# speculator_major_mainboard_96mm_v2_1.net
KiCad netlist of a schematic drawn in EAGLE
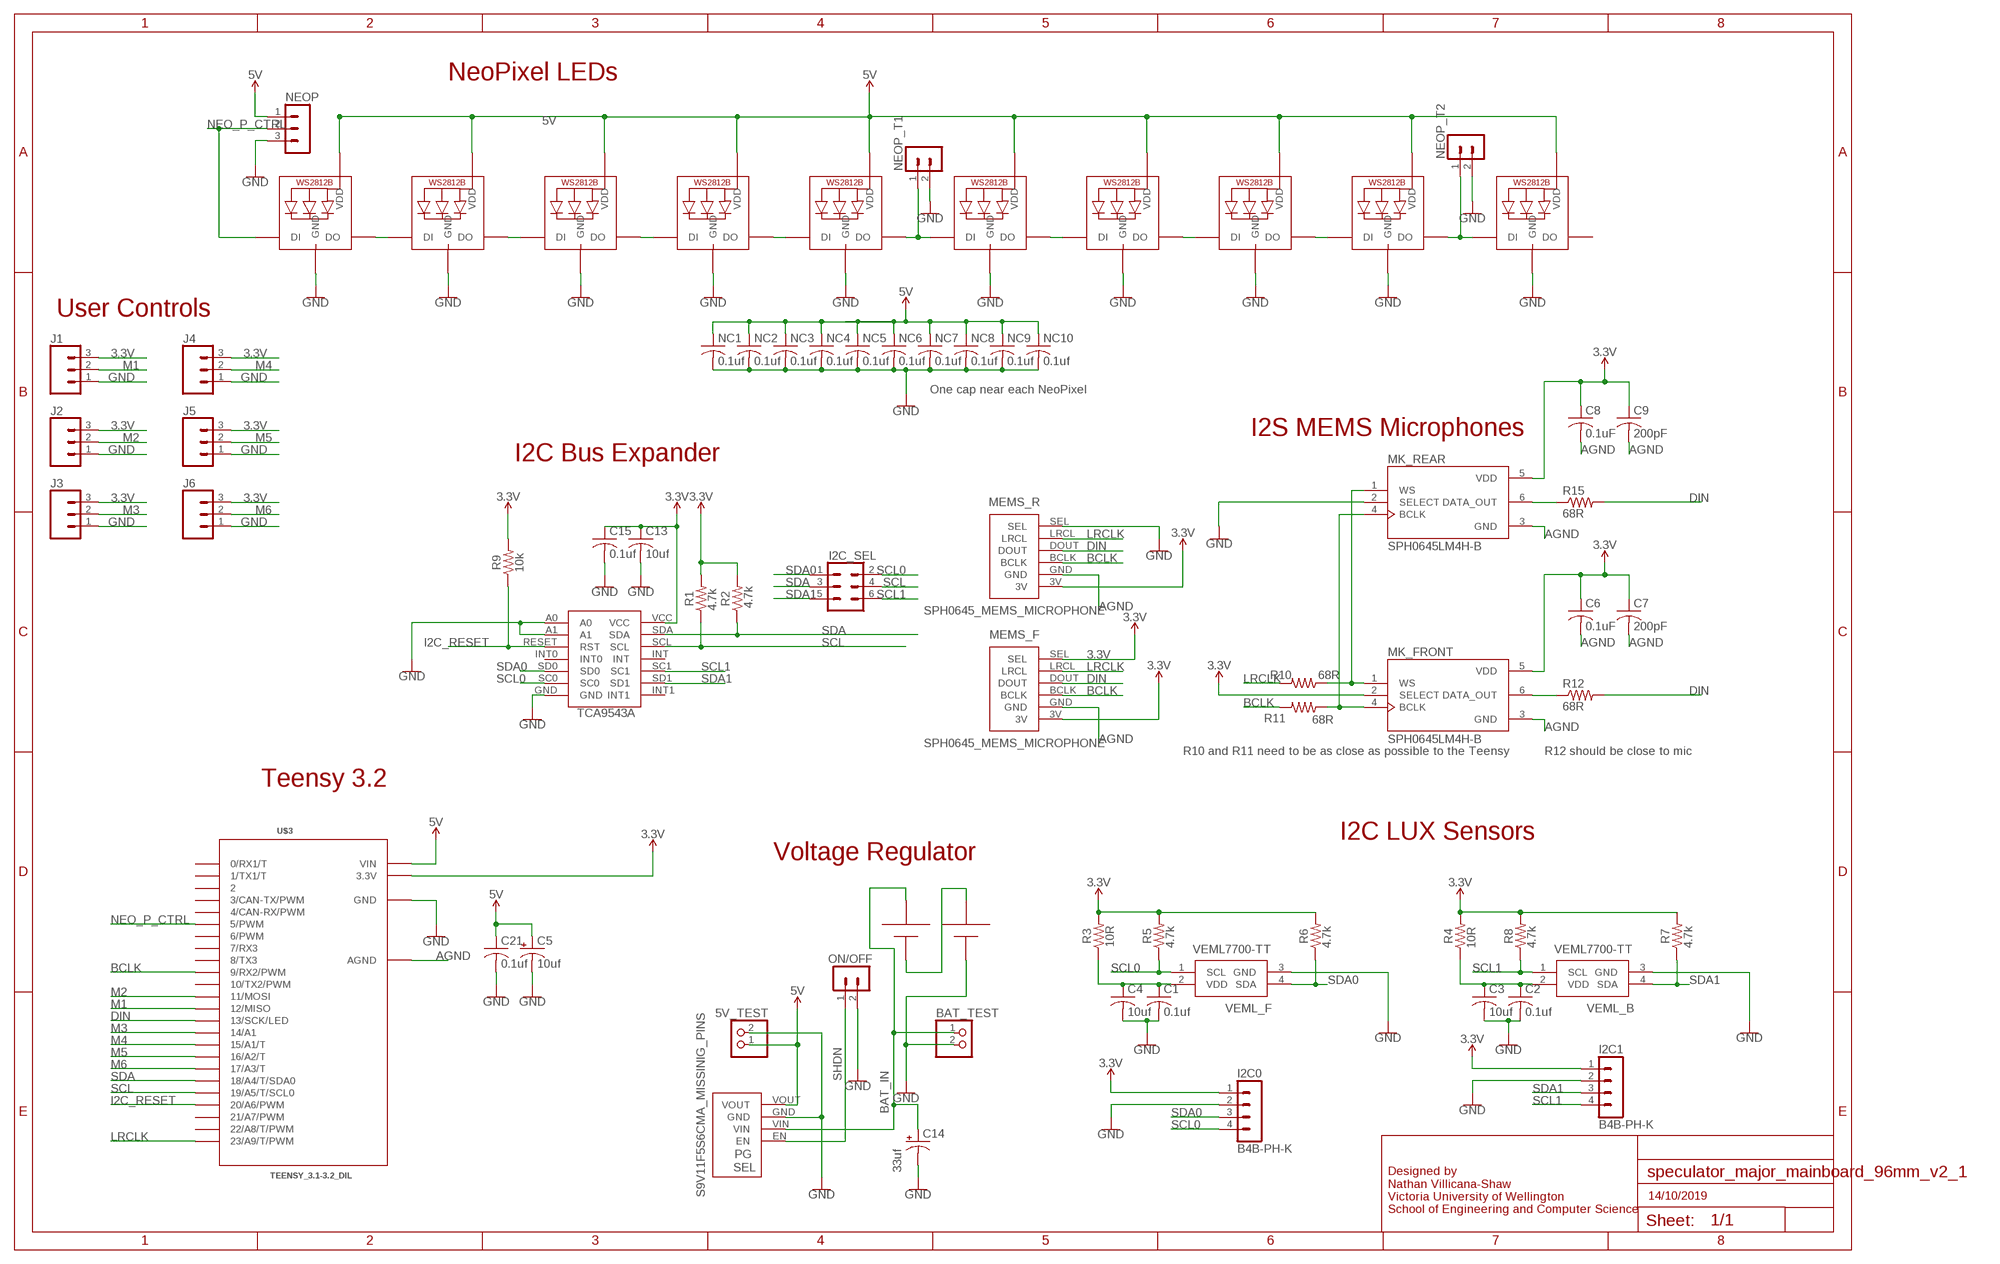
[diagram p0: schematic, sheet 1]

(export (version "E")
  (design (tool "Eeschema 10.0.6"))
  (components
    (comp (ref "5V_TEST")
      (value "PINHD-1X2")
      (footprint "eagle-import:1X02")
      (libsource (lib "eagle-import") (part "PINHD-1X2"))
    )
    (comp (ref "BAT_TEST")
      (value "PINHD-1X2")
      (footprint "eagle-import:1X02")
      (libsource (lib "eagle-import") (part "PINHD-1X2"))
    )
    (comp (ref "C1")
      (value "0.1uf")
      (footprint "eagle-import:C1206K")
      (libsource (lib "eagle-import") (part "C-USC1206K"))
    )
    (comp (ref "C2")
      (value "0.1uf")
      (footprint "eagle-import:C1206K")
      (libsource (lib "eagle-import") (part "C-USC1206K"))
    )
    (comp (ref "C3")
      (value "10uf")
      (footprint "eagle-import:C1206K")
      (libsource (lib "eagle-import") (part "C-USC1206K"))
    )
    (comp (ref "C4")
      (value "10uf")
      (footprint "eagle-import:C1206K")
      (libsource (lib "eagle-import") (part "C-USC1206K"))
    )
    (comp (ref "C5")
      (value "10uf")
      (footprint "eagle-import:E2,5-6")
      (libsource (lib "eagle-import") (part "CPOL-USE2.5-6"))
    )
    (comp (ref "C6")
      (value "0.1uF")
      (footprint "eagle-import:C1206K")
      (libsource (lib "eagle-import") (part "C-USC1206K"))
    )
    (comp (ref "C7")
      (value "200pF")
      (footprint "eagle-import:C1206K")
      (libsource (lib "eagle-import") (part "C-USC1206K"))
    )
    (comp (ref "C8")
      (value "0.1uF")
      (footprint "eagle-import:C1206K")
      (libsource (lib "eagle-import") (part "C-USC1206K"))
    )
    (comp (ref "C9")
      (value "200pF")
      (footprint "eagle-import:C1206K")
      (libsource (lib "eagle-import") (part "C-USC1206K"))
    )
    (comp (ref "C13")
      (value "10uf")
      (footprint "eagle-import:C1206K")
      (libsource (lib "eagle-import") (part "C-USC1206K"))
    )
    (comp (ref "C14")
      (value "33uf")
      (footprint "eagle-import:E2-5")
      (libsource (lib "eagle-import") (part "CPOL-USE2-5"))
    )
    (comp (ref "C15")
      (value "0.1uf")
      (footprint "eagle-import:C1206K")
      (libsource (lib "eagle-import") (part "C-USC1206K"))
    )
    (comp (ref "C21")
      (value "0.1uf")
      (footprint "eagle-import:C1206K")
      (libsource (lib "eagle-import") (part "C-USC1206K"))
    )
    (comp (ref "I2C0")
      (value "B4B-PH-K")
      (footprint "eagle-import:B4B-PH-K")
      (libsource (lib "eagle-import") (part "B4B-PH-K"))
    )
    (comp (ref "I2C1")
      (value "B4B-PH-K")
      (footprint "eagle-import:B4B-PH-K")
      (libsource (lib "eagle-import") (part "B4B-PH-K"))
    )
    (comp (ref "I2C_SEL")
      (value "FEMALE 2x3")
      (footprint "eagle-import:2X3")
      (libsource (lib "eagle-import") (part "CONN_03X2FEMALE"))
    )
    (comp (ref "J1")
      (value "CONN_03")
      (footprint "eagle-import:1X03")
      (libsource (lib "eagle-import") (part "CONN_03"))
    )
    (comp (ref "J2")
      (value "CONN_03")
      (footprint "eagle-import:1X03")
      (libsource (lib "eagle-import") (part "CONN_03"))
    )
    (comp (ref "J3")
      (value "CONN_03")
      (footprint "eagle-import:1X03")
      (libsource (lib "eagle-import") (part "CONN_03"))
    )
    (comp (ref "J4")
      (value "CONN_03")
      (footprint "eagle-import:1X03")
      (libsource (lib "eagle-import") (part "CONN_03"))
    )
    (comp (ref "J5")
      (value "CONN_03")
      (footprint "eagle-import:1X03")
      (libsource (lib "eagle-import") (part "CONN_03"))
    )
    (comp (ref "J6")
      (value "CONN_03")
      (footprint "eagle-import:1X03")
      (libsource (lib "eagle-import") (part "CONN_03"))
    )
    (comp (ref "MEMS_F")
      (value "SPH0645_MEMS_MICROPHONE")
      (footprint "eagle-import:SPH0645")
      (libsource (lib "eagle-import") (part "SPH0645_MEMS_MICROPHONE"))
    )
    (comp (ref "MEMS_R")
      (value "SPH0645_MEMS_MICROPHONE")
      (footprint "eagle-import:SPH0645")
      (libsource (lib "eagle-import") (part "SPH0645_MEMS_MICROPHONE"))
    )
    (comp (ref "MK_FRONT")
      (value "SPH0645LM4H-B")
      (footprint "eagle-import:MIC_SPH0645LM4H-B")
      (fields (field (name "DIGI-KEY_PART_NUMBER") "423-1405-1-ND") (field (name "MF") "Knowles"))
      (libsource (lib "eagle-import") (part "SPH0645LM4H-B"))
    )
    (comp (ref "MK_REAR")
      (value "SPH0645LM4H-B")
      (footprint "eagle-import:MIC_SPH0645LM4H-B")
      (fields (field (name "DIGI-KEY_PART_NUMBER") "423-1405-1-ND") (field (name "MF") "Knowles"))
      (libsource (lib "eagle-import") (part "SPH0645LM4H-B"))
    )
    (comp (ref "NC1")
      (value "0.1uf")
      (footprint "eagle-import:C1206K")
      (libsource (lib "eagle-import") (part "C-USC1206K"))
    )
    (comp (ref "NC2")
      (value "0.1uf")
      (footprint "eagle-import:C1206K")
      (libsource (lib "eagle-import") (part "C-USC1206K"))
    )
    (comp (ref "NC3")
      (value "0.1uf")
      (footprint "eagle-import:C1206K")
      (libsource (lib "eagle-import") (part "C-USC1206K"))
    )
    (comp (ref "NC4")
      (value "0.1uf")
      (footprint "eagle-import:C1206K")
      (libsource (lib "eagle-import") (part "C-USC1206K"))
    )
    (comp (ref "NC5")
      (value "0.1uf")
      (footprint "eagle-import:C1206K")
      (libsource (lib "eagle-import") (part "C-USC1206K"))
    )
    (comp (ref "NC6")
      (value "0.1uf")
      (footprint "eagle-import:C1206K")
      (libsource (lib "eagle-import") (part "C-USC1206K"))
    )
    (comp (ref "NC7")
      (value "0.1uf")
      (footprint "eagle-import:C1206K")
      (libsource (lib "eagle-import") (part "C-USC1206K"))
    )
    (comp (ref "NC8")
      (value "0.1uf")
      (footprint "eagle-import:C1206K")
      (libsource (lib "eagle-import") (part "C-USC1206K"))
    )
    (comp (ref "NC9")
      (value "0.1uf")
      (footprint "eagle-import:C1206K")
      (libsource (lib "eagle-import") (part "C-USC1206K"))
    )
    (comp (ref "NC10")
      (value "0.1uf")
      (footprint "eagle-import:C1206K")
      (libsource (lib "eagle-import") (part "C-USC1206K"))
    )
    (comp (ref "NEO1")
      (value "WS2812B5050")
      (footprint "eagle-import:WS2812B")
      (libsource (lib "eagle-import") (part "WS2812B5050"))
    )
    (comp (ref "NEO2")
      (value "WS2812B5050")
      (footprint "eagle-import:WS2812B")
      (libsource (lib "eagle-import") (part "WS2812B5050"))
    )
    (comp (ref "NEO3")
      (value "WS2812B5050")
      (footprint "eagle-import:WS2812B")
      (libsource (lib "eagle-import") (part "WS2812B5050"))
    )
    (comp (ref "NEO4")
      (value "WS2812B5050")
      (footprint "eagle-import:WS2812B")
      (libsource (lib "eagle-import") (part "WS2812B5050"))
    )
    (comp (ref "NEO5")
      (value "WS2812B5050")
      (footprint "eagle-import:WS2812B")
      (libsource (lib "eagle-import") (part "WS2812B5050"))
    )
    (comp (ref "NEO6")
      (value "WS2812B5050")
      (footprint "eagle-import:WS2812B")
      (libsource (lib "eagle-import") (part "WS2812B5050"))
    )
    (comp (ref "NEO7")
      (value "WS2812B5050")
      (footprint "eagle-import:WS2812B")
      (libsource (lib "eagle-import") (part "WS2812B5050"))
    )
    (comp (ref "NEO8")
      (value "WS2812B5050")
      (footprint "eagle-import:WS2812B")
      (libsource (lib "eagle-import") (part "WS2812B5050"))
    )
    (comp (ref "NEO9")
      (value "WS2812B5050")
      (footprint "eagle-import:WS2812B")
      (libsource (lib "eagle-import") (part "WS2812B5050"))
    )
    (comp (ref "NEO10")
      (value "WS2812B5050")
      (footprint "eagle-import:WS2812B")
      (libsource (lib "eagle-import") (part "WS2812B5050"))
    )
    (comp (ref "NEOP")
      (value "B3B-PH-K")
      (footprint "eagle-import:B3B-PH-K")
      (libsource (lib "eagle-import") (part "B3B-PH-K"))
    )
    (comp (ref "NEOP_T1")
      (value "B2B-PH-K")
      (footprint "eagle-import:B2B-PH-K")
      (libsource (lib "eagle-import") (part "B2B-PH-K"))
    )
    (comp (ref "NEOP_T2")
      (value "B2B-PH-K")
      (footprint "eagle-import:B2B-PH-K")
      (libsource (lib "eagle-import") (part "B2B-PH-K"))
    )
    (comp (ref "ON/OFF")
      (value "B2B-PH-K")
      (footprint "eagle-import:B2B-PH-K")
      (libsource (lib "eagle-import") (part "B2B-PH-K"))
    )
    (comp (ref "R1")
      (value "4.7k")
      (footprint "eagle-import:R1206W")
      (libsource (lib "eagle-import") (part "R-US_R1206W"))
    )
    (comp (ref "R2")
      (value "4.7k")
      (footprint "eagle-import:R1206W")
      (libsource (lib "eagle-import") (part "R-US_R1206W"))
    )
    (comp (ref "R3")
      (value "10R")
      (footprint "eagle-import:R1206W")
      (libsource (lib "eagle-import") (part "R-US_R1206W"))
    )
    (comp (ref "R4")
      (value "10R")
      (footprint "eagle-import:R1206W")
      (libsource (lib "eagle-import") (part "R-US_R1206W"))
    )
    (comp (ref "R5")
      (value "4.7k")
      (footprint "eagle-import:R1206W")
      (libsource (lib "eagle-import") (part "R-US_R1206W"))
    )
    (comp (ref "R6")
      (value "4.7k")
      (footprint "eagle-import:R1206W")
      (libsource (lib "eagle-import") (part "R-US_R1206W"))
    )
    (comp (ref "R7")
      (value "4.7k")
      (footprint "eagle-import:R1206W")
      (libsource (lib "eagle-import") (part "R-US_R1206W"))
    )
    (comp (ref "R8")
      (value "4.7k")
      (footprint "eagle-import:R1206W")
      (libsource (lib "eagle-import") (part "R-US_R1206W"))
    )
    (comp (ref "R9")
      (value "10k")
      (footprint "eagle-import:R1206W")
      (libsource (lib "eagle-import") (part "R-US_R1206W"))
    )
    (comp (ref "R10")
      (value "68R")
      (footprint "eagle-import:M1206")
      (libsource (lib "eagle-import") (part "R-US_M1206"))
    )
    (comp (ref "R11")
      (value "68R")
      (footprint "eagle-import:M1206")
      (libsource (lib "eagle-import") (part "R-US_M1206"))
    )
    (comp (ref "R12")
      (value "68R")
      (footprint "eagle-import:M1206")
      (libsource (lib "eagle-import") (part "R-US_M1206"))
    )
    (comp (ref "R15")
      (value "68R")
      (footprint "eagle-import:M1206")
      (libsource (lib "eagle-import") (part "R-US_M1206"))
    )
    (comp (ref "U$1")
      (value "TCA9543A")
      (footprint "eagle-import:SO14")
      (libsource (lib "eagle-import") (part "TCA9543A"))
    )
    (comp (ref "U$2")
      (value "BK-18650-PC4")
      (footprint "eagle-import:18650-PC4")
      (fields (field (name "MF") "MPD"))
      (libsource (lib "eagle-import") (part "BK-18650-PC4"))
    )
    (comp (ref "U$3")
      (value "TEENSY_3.1-3.2_DIL")
      (footprint "eagle-import:TEENSY_3.0-3.2&LC_DIL")
      (libsource (lib "eagle-import") (part "TEENSY_3.1-3.2_DIL"))
    )
    (comp (ref "U$6")
      (value "S9V11F5S6CMA_MISSINIG_PINS")
      (footprint "eagle-import:S9V11F3S5CMA_MISSING_PINS")
      (libsource (lib "eagle-import") (part "S9V11F5S6CMA_MISSINIG_PINS"))
    )
    (comp (ref "VEML_B")
      (value "VEML7700-TT")
      (footprint "eagle-import:VEML7700")
      (fields (field (name "MOUSER_PART_NUMBER") "78-VEML7700-TT") (field (name "RS_PART_NUMBER") "1226791P"))
      (libsource (lib "eagle-import") (part "VEML7700-TT"))
    )
    (comp (ref "VEML_F")
      (value "VEML7700-TT")
      (footprint "eagle-import:VEML7700")
      (fields (field (name "MOUSER_PART_NUMBER") "78-VEML7700-TT") (field (name "RS_PART_NUMBER") "1226791P"))
      (libsource (lib "eagle-import") (part "VEML7700-TT"))
    )
  )
  (nets
    (net (code "1") (name "/AGND") (class "Default")
      (node (ref "C6") (pin "2") (pinfunction "2_2") (pintype "passive"))
      (node (ref "C7") (pin "2") (pinfunction "2_2") (pintype "passive"))
      (node (ref "C8") (pin "2") (pinfunction "2_2") (pintype "passive"))
      (node (ref "C9") (pin "2") (pinfunction "2_2") (pintype "passive"))
      (node (ref "MEMS_F") (pin "GND") (pinfunction "GND_GND") (pintype "bidirectional"))
      (node (ref "MEMS_R") (pin "GND") (pinfunction "GND_GND") (pintype "bidirectional"))
      (node (ref "MK_FRONT") (pin "3") (pinfunction "GND_3") (pintype "power_in"))
      (node (ref "MK_REAR") (pin "3") (pinfunction "GND_3") (pintype "power_in"))
      (node (ref "U$3") (pin "AGND") (pinfunction "AGND_AGND") (pintype "power_in"))
    )
    (net (code "2") (name "/BAT_IN") (class "Default")
      (node (ref "BAT_TEST") (pin "1") (pinfunction "1_1") (pintype "passive"))
      (node (ref "C14") (pin "+") (pinfunction "+_+") (pintype "passive"))
      (node (ref "U$2") (pin "+1") (pinfunction "+1_+1") (pintype "bidirectional"))
      (node (ref "U$6") (pin "VIN") (pinfunction "VIN_VIN") (pintype "bidirectional"))
    )
    (net (code "3") (name "/BCLK") (class "Default")
      (node (ref "MEMS_F") (pin "BCLK") (pinfunction "BCLK_BCLK") (pintype "bidirectional"))
      (node (ref "MEMS_R") (pin "BCLK") (pinfunction "BCLK_BCLK") (pintype "bidirectional"))
      (node (ref "R11") (pin "2") (pinfunction "2_2") (pintype "passive"))
      (node (ref "U$3") (pin "9") (pinfunction "9/RX2/PWM_9") (pintype "bidirectional"))
    )
    (net (code "4") (name "/DIN") (class "Default")
      (node (ref "MEMS_F") (pin "DOUT") (pinfunction "DOUT_DOUT") (pintype "bidirectional"))
      (node (ref "MEMS_R") (pin "DOUT") (pinfunction "DOUT_DOUT") (pintype "bidirectional"))
      (node (ref "R12") (pin "2") (pinfunction "2_2") (pintype "passive"))
      (node (ref "R15") (pin "2") (pinfunction "2_2") (pintype "passive"))
      (node (ref "U$3") (pin "13") (pinfunction "13/SCK/LED_13") (pintype "bidirectional"))
    )
    (net (code "5") (name "/I2C_RESET") (class "Default")
      (node (ref "R9") (pin "1") (pinfunction "1_1") (pintype "passive"))
      (node (ref "U$1") (pin "RESET") (pinfunction "RST_RESET") (pintype "bidirectional"))
      (node (ref "U$3") (pin "20/A6") (pinfunction "20/A6/PWM_20/A6") (pintype "bidirectional"))
    )
    (net (code "6") (name "/LRCLK") (class "Default")
      (node (ref "MEMS_F") (pin "LRCL") (pinfunction "LRCL_LRCL") (pintype "bidirectional"))
      (node (ref "MEMS_R") (pin "LRCL") (pinfunction "LRCL_LRCL") (pintype "bidirectional"))
      (node (ref "R10") (pin "2") (pinfunction "2_2") (pintype "passive"))
      (node (ref "U$3") (pin "23/A9") (pinfunction "23/A9/T/PWM_23/A9") (pintype "bidirectional"))
    )
    (net (code "7") (name "/M1") (class "Default")
      (node (ref "J1") (pin "2") (pinfunction "2_2") (pintype "passive"))
      (node (ref "U$3") (pin "12") (pinfunction "12/MISO_12") (pintype "bidirectional"))
    )
    (net (code "8") (name "/M2") (class "Default")
      (node (ref "J2") (pin "2") (pinfunction "2_2") (pintype "passive"))
      (node (ref "U$3") (pin "11") (pinfunction "11/MOSI_11") (pintype "bidirectional"))
    )
    (net (code "9") (name "/M3") (class "Default")
      (node (ref "J3") (pin "2") (pinfunction "2_2") (pintype "passive"))
      (node (ref "U$3") (pin "14/A0") (pinfunction "14/A1_14/A0") (pintype "bidirectional"))
    )
    (net (code "10") (name "/M4") (class "Default")
      (node (ref "J4") (pin "2") (pinfunction "2_2") (pintype "passive"))
      (node (ref "U$3") (pin "15/A1") (pinfunction "15/A1/T_15/A1") (pintype "bidirectional"))
    )
    (net (code "11") (name "/M5") (class "Default")
      (node (ref "J5") (pin "2") (pinfunction "2_2") (pintype "passive"))
      (node (ref "U$3") (pin "16/A2") (pinfunction "16/A2/T_16/A2") (pintype "bidirectional"))
    )
    (net (code "12") (name "/M6") (class "Default")
      (node (ref "J6") (pin "2") (pinfunction "2_2") (pintype "passive"))
      (node (ref "U$3") (pin "17/A3") (pinfunction "17/A3/T_17/A3") (pintype "bidirectional"))
    )
    (net (code "13") (name "/NEO_P_CTRL") (class "Default")
      (node (ref "NEO1") (pin "4-DIN") (pinfunction "DI_4-DIN") (pintype "input"))
      (node (ref "NEOP") (pin "2") (pinfunction "2_2") (pintype "passive"))
      (node (ref "U$3") (pin "5") (pinfunction "5/PWM_5") (pintype "bidirectional"))
    )
    (net (code "14") (name "/SCL") (class "Default")
      (node (ref "I2C_SEL") (pin "4") (pinfunction "4_4") (pintype "bidirectional"))
      (node (ref "R1") (pin "1") (pinfunction "1_1") (pintype "passive"))
      (node (ref "U$1") (pin "SCL") (pinfunction "SCL_SCL") (pintype "bidirectional"))
      (node (ref "U$3") (pin "19/A5") (pinfunction "19/A5/T/SCL0_19/A5") (pintype "bidirectional"))
    )
    (net (code "15") (name "/SCL0") (class "Default")
      (node (ref "I2C0") (pin "4") (pinfunction "4_4") (pintype "passive"))
      (node (ref "I2C_SEL") (pin "2") (pinfunction "2_2") (pintype "bidirectional"))
      (node (ref "R5") (pin "1") (pinfunction "1_1") (pintype "passive"))
      (node (ref "U$1") (pin "SC0") (pinfunction "SC0_SC0") (pintype "bidirectional"))
      (node (ref "VEML_F") (pin "1") (pinfunction "SCL_1") (pintype "bidirectional"))
    )
    (net (code "16") (name "/SCL1") (class "Default")
      (node (ref "I2C1") (pin "4") (pinfunction "4_4") (pintype "passive"))
      (node (ref "I2C_SEL") (pin "6") (pinfunction "6_6") (pintype "bidirectional"))
      (node (ref "R8") (pin "1") (pinfunction "1_1") (pintype "passive"))
      (node (ref "U$1") (pin "SC1") (pinfunction "SC1_SC1") (pintype "bidirectional"))
      (node (ref "VEML_B") (pin "1") (pinfunction "SCL_1") (pintype "bidirectional"))
    )
    (net (code "17") (name "/SDA") (class "Default")
      (node (ref "I2C_SEL") (pin "3") (pinfunction "3_3") (pintype "bidirectional"))
      (node (ref "R2") (pin "1") (pinfunction "1_1") (pintype "passive"))
      (node (ref "U$1") (pin "SDA") (pinfunction "SDA_SDA") (pintype "bidirectional"))
      (node (ref "U$3") (pin "18/A4") (pinfunction "18/A4/T/SDA0_18/A4") (pintype "bidirectional"))
    )
    (net (code "18") (name "/SDA0") (class "Default")
      (node (ref "I2C0") (pin "3") (pinfunction "3_3") (pintype "passive"))
      (node (ref "I2C_SEL") (pin "1") (pinfunction "1_1") (pintype "bidirectional"))
      (node (ref "R6") (pin "1") (pinfunction "1_1") (pintype "passive"))
      (node (ref "U$1") (pin "SD0") (pinfunction "SD0_SD0") (pintype "bidirectional"))
      (node (ref "VEML_F") (pin "4") (pinfunction "SDA_4") (pintype "bidirectional"))
    )
    (net (code "19") (name "/SDA1") (class "Default")
      (node (ref "I2C1") (pin "3") (pinfunction "3_3") (pintype "passive"))
      (node (ref "I2C_SEL") (pin "5") (pinfunction "5_5") (pintype "bidirectional"))
      (node (ref "R7") (pin "1") (pinfunction "1_1") (pintype "passive"))
      (node (ref "U$1") (pin "SD1") (pinfunction "SD1_SD1") (pintype "bidirectional"))
      (node (ref "VEML_B") (pin "4") (pinfunction "SDA_4") (pintype "bidirectional"))
    )
    (net (code "20") (name "/SHDN") (class "Default")
      (node (ref "ON/OFF") (pin "1") (pinfunction "1_1") (pintype "passive"))
      (node (ref "U$6") (pin "EN") (pinfunction "EN_EN") (pintype "bidirectional"))
    )
    (net (code "21") (name "3.3V") (class "Default")
      (node (ref "C13") (pin "1") (pinfunction "1_1") (pintype "passive"))
      (node (ref "C15") (pin "1") (pinfunction "1_1") (pintype "passive"))
      (node (ref "C6") (pin "1") (pinfunction "1_1") (pintype "passive"))
      (node (ref "C7") (pin "1") (pinfunction "1_1") (pintype "passive"))
      (node (ref "C8") (pin "1") (pinfunction "1_1") (pintype "passive"))
      (node (ref "C9") (pin "1") (pinfunction "1_1") (pintype "passive"))
      (node (ref "I2C0") (pin "1") (pinfunction "1_1") (pintype "passive"))
      (node (ref "I2C1") (pin "1") (pinfunction "1_1") (pintype "passive"))
      (node (ref "J1") (pin "3") (pinfunction "3_3") (pintype "passive"))
      (node (ref "J2") (pin "3") (pinfunction "3_3") (pintype "passive"))
      (node (ref "J3") (pin "3") (pinfunction "3_3") (pintype "passive"))
      (node (ref "J4") (pin "3") (pinfunction "3_3") (pintype "passive"))
      (node (ref "J5") (pin "3") (pinfunction "3_3") (pintype "passive"))
      (node (ref "J6") (pin "3") (pinfunction "3_3") (pintype "passive"))
      (node (ref "MEMS_F") (pin "3V") (pinfunction "3V_3V") (pintype "bidirectional"))
      (node (ref "MEMS_F") (pin "SEL") (pinfunction "SEL_SEL") (pintype "bidirectional"))
      (node (ref "MEMS_R") (pin "3V") (pinfunction "3V_3V") (pintype "bidirectional"))
      (node (ref "MK_FRONT") (pin "2") (pinfunction "SELECT_2") (pintype "input"))
      (node (ref "MK_FRONT") (pin "5") (pinfunction "VDD_5") (pintype "power_in"))
      (node (ref "MK_REAR") (pin "5") (pinfunction "VDD_5") (pintype "power_in"))
      (node (ref "R1") (pin "2") (pinfunction "2_2") (pintype "passive"))
      (node (ref "R2") (pin "2") (pinfunction "2_2") (pintype "passive"))
      (node (ref "R3") (pin "2") (pinfunction "2_2") (pintype "passive"))
      (node (ref "R4") (pin "2") (pinfunction "2_2") (pintype "passive"))
      (node (ref "R5") (pin "2") (pinfunction "2_2") (pintype "passive"))
      (node (ref "R6") (pin "2") (pinfunction "2_2") (pintype "passive"))
      (node (ref "R7") (pin "2") (pinfunction "2_2") (pintype "passive"))
      (node (ref "R8") (pin "2") (pinfunction "2_2") (pintype "passive"))
      (node (ref "R9") (pin "2") (pinfunction "2_2") (pintype "passive"))
      (node (ref "U$1") (pin "VCC") (pinfunction "VCC_VCC") (pintype "bidirectional"))
      (node (ref "U$3") (pin "3.3V") (pinfunction "3.3V_3.3V") (pintype "power_in"))
    )
    (net (code "22") (name "5V") (class "Default")
      (node (ref "5V_TEST") (pin "1") (pinfunction "1_1") (pintype "passive"))
      (node (ref "C21") (pin "1") (pinfunction "1_1") (pintype "passive"))
      (node (ref "C5") (pin "+") (pinfunction "+_+") (pintype "passive"))
      (node (ref "NC1") (pin "1") (pinfunction "1_1") (pintype "passive"))
      (node (ref "NC10") (pin "1") (pinfunction "1_1") (pintype "passive"))
      (node (ref "NC2") (pin "1") (pinfunction "1_1") (pintype "passive"))
      (node (ref "NC3") (pin "1") (pinfunction "1_1") (pintype "passive"))
      (node (ref "NC4") (pin "1") (pinfunction "1_1") (pintype "passive"))
      (node (ref "NC5") (pin "1") (pinfunction "1_1") (pintype "passive"))
      (node (ref "NC6") (pin "1") (pinfunction "1_1") (pintype "passive"))
      (node (ref "NC7") (pin "1") (pinfunction "1_1") (pintype "passive"))
      (node (ref "NC8") (pin "1") (pinfunction "1_1") (pintype "passive"))
      (node (ref "NC9") (pin "1") (pinfunction "1_1") (pintype "passive"))
      (node (ref "NEO1") (pin "1-VDD") (pinfunction "VDD_1-VDD") (pintype "power_in"))
      (node (ref "NEO10") (pin "1-VDD") (pinfunction "VDD_1-VDD") (pintype "power_in"))
      (node (ref "NEO2") (pin "1-VDD") (pinfunction "VDD_1-VDD") (pintype "power_in"))
      (node (ref "NEO3") (pin "1-VDD") (pinfunction "VDD_1-VDD") (pintype "power_in"))
      (node (ref "NEO4") (pin "1-VDD") (pinfunction "VDD_1-VDD") (pintype "power_in"))
      (node (ref "NEO5") (pin "1-VDD") (pinfunction "VDD_1-VDD") (pintype "power_in"))
      (node (ref "NEO6") (pin "1-VDD") (pinfunction "VDD_1-VDD") (pintype "power_in"))
      (node (ref "NEO7") (pin "1-VDD") (pinfunction "VDD_1-VDD") (pintype "power_in"))
      (node (ref "NEO8") (pin "1-VDD") (pinfunction "VDD_1-VDD") (pintype "power_in"))
      (node (ref "NEO9") (pin "1-VDD") (pinfunction "VDD_1-VDD") (pintype "power_in"))
      (node (ref "NEOP") (pin "1") (pinfunction "1_1") (pintype "passive"))
      (node (ref "U$3") (pin "VIN") (pinfunction "VIN_VIN") (pintype "power_in"))
      (node (ref "U$6") (pin "VOUT") (pinfunction "VOUT_VOUT") (pintype "bidirectional"))
    )
    (net (code "23") (name "GND") (class "Default")
      (node (ref "5V_TEST") (pin "2") (pinfunction "2_2") (pintype "passive"))
      (node (ref "BAT_TEST") (pin "2") (pinfunction "2_2") (pintype "passive"))
      (node (ref "C1") (pin "2") (pinfunction "2_2") (pintype "passive"))
      (node (ref "C13") (pin "2") (pinfunction "2_2") (pintype "passive"))
      (node (ref "C14") (pin "-") (pinfunction "-_-") (pintype "passive"))
      (node (ref "C15") (pin "2") (pinfunction "2_2") (pintype "passive"))
      (node (ref "C2") (pin "2") (pinfunction "2_2") (pintype "passive"))
      (node (ref "C21") (pin "2") (pinfunction "2_2") (pintype "passive"))
      (node (ref "C3") (pin "2") (pinfunction "2_2") (pintype "passive"))
      (node (ref "C4") (pin "2") (pinfunction "2_2") (pintype "passive"))
      (node (ref "C5") (pin "-") (pinfunction "-_-") (pintype "passive"))
      (node (ref "I2C0") (pin "2") (pinfunction "2_2") (pintype "passive"))
      (node (ref "I2C1") (pin "2") (pinfunction "2_2") (pintype "passive"))
      (node (ref "J1") (pin "1") (pinfunction "1_1") (pintype "passive"))
      (node (ref "J2") (pin "1") (pinfunction "1_1") (pintype "passive"))
      (node (ref "J3") (pin "1") (pinfunction "1_1") (pintype "passive"))
      (node (ref "J4") (pin "1") (pinfunction "1_1") (pintype "passive"))
      (node (ref "J5") (pin "1") (pinfunction "1_1") (pintype "passive"))
      (node (ref "J6") (pin "1") (pinfunction "1_1") (pintype "passive"))
      (node (ref "MEMS_R") (pin "SEL") (pinfunction "SEL_SEL") (pintype "bidirectional"))
      (node (ref "MK_REAR") (pin "2") (pinfunction "SELECT_2") (pintype "input"))
      (node (ref "NC1") (pin "2") (pinfunction "2_2") (pintype "passive"))
      (node (ref "NC10") (pin "2") (pinfunction "2_2") (pintype "passive"))
      (node (ref "NC2") (pin "2") (pinfunction "2_2") (pintype "passive"))
      (node (ref "NC3") (pin "2") (pinfunction "2_2") (pintype "passive"))
      (node (ref "NC4") (pin "2") (pinfunction "2_2") (pintype "passive"))
      (node (ref "NC5") (pin "2") (pinfunction "2_2") (pintype "passive"))
      (node (ref "NC6") (pin "2") (pinfunction "2_2") (pintype "passive"))
      (node (ref "NC7") (pin "2") (pinfunction "2_2") (pintype "passive"))
      (node (ref "NC8") (pin "2") (pinfunction "2_2") (pintype "passive"))
      (node (ref "NC9") (pin "2") (pinfunction "2_2") (pintype "passive"))
      (node (ref "NEO1") (pin "3-GND") (pinfunction "GND_3-GND") (pintype "power_in"))
      (node (ref "NEO10") (pin "3-GND") (pinfunction "GND_3-GND") (pintype "power_in"))
      (node (ref "NEO2") (pin "3-GND") (pinfunction "GND_3-GND") (pintype "power_in"))
      (node (ref "NEO3") (pin "3-GND") (pinfunction "GND_3-GND") (pintype "power_in"))
      (node (ref "NEO4") (pin "3-GND") (pinfunction "GND_3-GND") (pintype "power_in"))
      (node (ref "NEO5") (pin "3-GND") (pinfunction "GND_3-GND") (pintype "power_in"))
      (node (ref "NEO6") (pin "3-GND") (pinfunction "GND_3-GND") (pintype "power_in"))
      (node (ref "NEO7") (pin "3-GND") (pinfunction "GND_3-GND") (pintype "power_in"))
      (node (ref "NEO8") (pin "3-GND") (pinfunction "GND_3-GND") (pintype "power_in"))
      (node (ref "NEO9") (pin "3-GND") (pinfunction "GND_3-GND") (pintype "power_in"))
      (node (ref "NEOP") (pin "3") (pinfunction "3_3") (pintype "passive"))
      (node (ref "NEOP_T1") (pin "2") (pinfunction "2_2") (pintype "passive"))
      (node (ref "NEOP_T2") (pin "2") (pinfunction "2_2") (pintype "passive"))
      (node (ref "ON/OFF") (pin "2") (pinfunction "2_2") (pintype "passive"))
      (node (ref "U$1") (pin "A0") (pinfunction "A0_A0") (pintype "bidirectional"))
      (node (ref "U$1") (pin "A1") (pinfunction "A1_A1") (pintype "bidirectional"))
      (node (ref "U$1") (pin "GND") (pinfunction "GND_GND") (pintype "bidirectional"))
      (node (ref "U$2") (pin "-2") (pinfunction "-2_-2") (pintype "bidirectional"))
      (node (ref "U$3") (pin "GND") (pinfunction "GND_GND") (pintype "power_in"))
      (node (ref "U$6") (pin "GND") (pinfunction "GND_GND") (pintype "bidirectional"))
      (node (ref "VEML_B") (pin "3") (pinfunction "GND_3") (pintype "bidirectional"))
      (node (ref "VEML_F") (pin "3") (pinfunction "GND_3") (pintype "bidirectional"))
    )
    (net (code "24") (name "Net-(MK_FRONT-BCLK)") (class "Default")
      (node (ref "MK_FRONT") (pin "4") (pinfunction "BCLK_4") (pintype "input"))
      (node (ref "MK_REAR") (pin "4") (pinfunction "BCLK_4") (pintype "input"))
      (node (ref "R11") (pin "1") (pinfunction "1_1") (pintype "passive"))
    )
    (net (code "25") (name "Net-(MK_FRONT-DATA_OUT)") (class "Default")
      (node (ref "MK_FRONT") (pin "6") (pinfunction "DATA_OUT_6") (pintype "output"))
      (node (ref "R12") (pin "1") (pinfunction "1_1") (pintype "passive"))
    )
    (net (code "26") (name "Net-(MK_FRONT-WS)") (class "Default")
      (node (ref "MK_FRONT") (pin "1") (pinfunction "WS_1") (pintype "input"))
      (node (ref "MK_REAR") (pin "1") (pinfunction "WS_1") (pintype "input"))
      (node (ref "R10") (pin "1") (pinfunction "1_1") (pintype "passive"))
    )
    (net (code "27") (name "Net-(MK_REAR-DATA_OUT)") (class "Default")
      (node (ref "MK_REAR") (pin "6") (pinfunction "DATA_OUT_6") (pintype "output"))
      (node (ref "R15") (pin "1") (pinfunction "1_1") (pintype "passive"))
    )
    (net (code "28") (name "Net-(NEO1-DO)") (class "Default")
      (node (ref "NEO1") (pin "2-DOUT") (pinfunction "DO_2-DOUT") (pintype "output"))
      (node (ref "NEO2") (pin "4-DIN") (pinfunction "DI_4-DIN") (pintype "input"))
    )
    (net (code "29") (name "Net-(NEO2-DO)") (class "Default")
      (node (ref "NEO2") (pin "2-DOUT") (pinfunction "DO_2-DOUT") (pintype "output"))
      (node (ref "NEO3") (pin "4-DIN") (pinfunction "DI_4-DIN") (pintype "input"))
    )
    (net (code "30") (name "Net-(NEO3-DO)") (class "Default")
      (node (ref "NEO3") (pin "2-DOUT") (pinfunction "DO_2-DOUT") (pintype "output"))
      (node (ref "NEO4") (pin "4-DIN") (pinfunction "DI_4-DIN") (pintype "input"))
    )
    (net (code "31") (name "Net-(NEO4-DO)") (class "Default")
      (node (ref "NEO4") (pin "2-DOUT") (pinfunction "DO_2-DOUT") (pintype "output"))
      (node (ref "NEO5") (pin "4-DIN") (pinfunction "DI_4-DIN") (pintype "input"))
    )
    (net (code "32") (name "Net-(NEO5-DO)") (class "Default")
      (node (ref "NEO5") (pin "2-DOUT") (pinfunction "DO_2-DOUT") (pintype "output"))
      (node (ref "NEO6") (pin "4-DIN") (pinfunction "DI_4-DIN") (pintype "input"))
      (node (ref "NEOP_T1") (pin "1") (pinfunction "1_1") (pintype "passive"))
    )
    (net (code "33") (name "Net-(NEO6-DO)") (class "Default")
      (node (ref "NEO6") (pin "2-DOUT") (pinfunction "DO_2-DOUT") (pintype "output"))
      (node (ref "NEO7") (pin "4-DIN") (pinfunction "DI_4-DIN") (pintype "input"))
    )
    (net (code "34") (name "Net-(NEO7-DO)") (class "Default")
      (node (ref "NEO7") (pin "2-DOUT") (pinfunction "DO_2-DOUT") (pintype "output"))
      (node (ref "NEO8") (pin "4-DIN") (pinfunction "DI_4-DIN") (pintype "input"))
    )
    (net (code "35") (name "Net-(NEO8-DO)") (class "Default")
      (node (ref "NEO8") (pin "2-DOUT") (pinfunction "DO_2-DOUT") (pintype "output"))
      (node (ref "NEO9") (pin "4-DIN") (pinfunction "DI_4-DIN") (pintype "input"))
    )
    (net (code "36") (name "Net-(NEO10-DI)") (class "Default")
      (node (ref "NEO10") (pin "4-DIN") (pinfunction "DI_4-DIN") (pintype "input"))
      (node (ref "NEO9") (pin "2-DOUT") (pinfunction "DO_2-DOUT") (pintype "output"))
      (node (ref "NEOP_T2") (pin "1") (pinfunction "1_1") (pintype "passive"))
    )
    (net (code "37") (name "Net-(U$2-Pad+2)") (class "Default")
      (node (ref "U$2") (pin "+2") (pinfunction "+2_+2") (pintype "bidirectional"))
      (node (ref "U$2") (pin "-1") (pinfunction "-1_-1") (pintype "bidirectional"))
    )
    (net (code "38") (name "Net-(VEML_B-VDD)") (class "Default")
      (node (ref "C2") (pin "1") (pinfunction "1_1") (pintype "passive"))
      (node (ref "C3") (pin "1") (pinfunction "1_1") (pintype "passive"))
      (node (ref "R4") (pin "1") (pinfunction "1_1") (pintype "passive"))
      (node (ref "VEML_B") (pin "2") (pinfunction "VDD_2") (pintype "bidirectional"))
    )
    (net (code "39") (name "Net-(VEML_F-VDD)") (class "Default")
      (node (ref "C1") (pin "1") (pinfunction "1_1") (pintype "passive"))
      (node (ref "C4") (pin "1") (pinfunction "1_1") (pintype "passive"))
      (node (ref "R3") (pin "1") (pinfunction "1_1") (pintype "passive"))
      (node (ref "VEML_F") (pin "2") (pinfunction "VDD_2") (pintype "bidirectional"))
    )
    (net (code "40") (name "unconnected-(NEO10-DO-Pad2-DOUT)") (class "Default")
      (node (ref "NEO10") (pin "2-DOUT") (pinfunction "DO_2-DOUT") (pintype "output"))
    )
    (net (code "41") (name "unconnected-(U$1-PadINT)") (class "Default")
      (node (ref "U$1") (pin "INT") (pinfunction "INT_INT") (pintype "bidirectional"))
    )
    (net (code "42") (name "unconnected-(U$1-PadINT0)") (class "Default")
      (node (ref "U$1") (pin "INT0") (pinfunction "INT0_INT0") (pintype "bidirectional"))
    )
    (net (code "43") (name "unconnected-(U$1-PadINT1)") (class "Default")
      (node (ref "U$1") (pin "INT1") (pinfunction "INT1_INT1") (pintype "bidirectional"))
    )
    (net (code "44") (name "unconnected-(U$3-0{slash}RX1{slash}T-Pad0)") (class "Default")
      (node (ref "U$3") (pin "0") (pinfunction "0/RX1/T_0") (pintype "bidirectional"))
    )
    (net (code "45") (name "unconnected-(U$3-1{slash}TX1{slash}T-Pad1)") (class "Default")
      (node (ref "U$3") (pin "1") (pinfunction "1/TX1/T_1") (pintype "bidirectional"))
    )
    (net (code "46") (name "unconnected-(U$3-3{slash}CAN-TX{slash}PWM-Pad3)") (class "Default")
      (node (ref "U$3") (pin "3") (pinfunction "3/CAN-TX/PWM_3") (pintype "bidirectional"))
    )
    (net (code "47") (name "unconnected-(U$3-4{slash}CAN-RX{slash}PWM-Pad4)") (class "Default")
      (node (ref "U$3") (pin "4") (pinfunction "4/CAN-RX/PWM_4") (pintype "bidirectional"))
    )
    (net (code "48") (name "unconnected-(U$3-6{slash}PWM-Pad6)") (class "Default")
      (node (ref "U$3") (pin "6") (pinfunction "6/PWM_6") (pintype "bidirectional"))
    )
    (net (code "49") (name "unconnected-(U$3-7{slash}RX3-Pad7)") (class "Default")
      (node (ref "U$3") (pin "7") (pinfunction "7/RX3_7") (pintype "bidirectional"))
    )
    (net (code "50") (name "unconnected-(U$3-8{slash}TX3-Pad8)") (class "Default")
      (node (ref "U$3") (pin "8") (pinfunction "8/TX3_8") (pintype "bidirectional"))
    )
    (net (code "51") (name "unconnected-(U$3-10{slash}TX2{slash}PWM-Pad10)") (class "Default")
      (node (ref "U$3") (pin "10") (pinfunction "10/TX2/PWM_10") (pintype "bidirectional"))
    )
    (net (code "52") (name "unconnected-(U$3-21{slash}A7{slash}PWM-Pad21{slash}A7)") (class "Default")
      (node (ref "U$3") (pin "21/A7") (pinfunction "21/A7/PWM_21/A7") (pintype "bidirectional"))
    )
    (net (code "53") (name "unconnected-(U$3-22{slash}A8{slash}T{slash}PWM-Pad22{slash}A8)") (class "Default")
      (node (ref "U$3") (pin "22/A8") (pinfunction "22/A8/T/PWM_22/A8") (pintype "bidirectional"))
    )
    (net (code "54") (name "unconnected-(U$3-Pad2)") (class "Default")
      (node (ref "U$3") (pin "2") (pinfunction "2_2") (pintype "bidirectional"))
    )
  )
)
